# bcan_adapter.net
KiCad netlist of a schematic drawn in Altium Designer
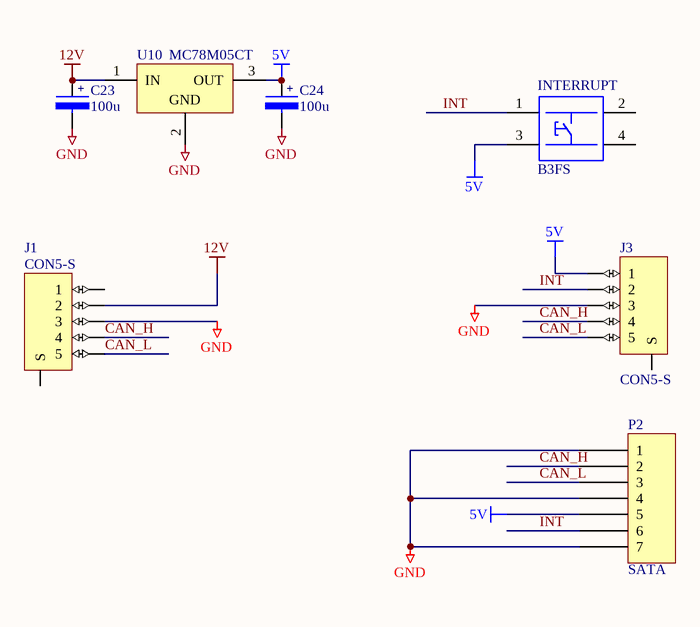
[diagram p0: bcan_adapter.SchDoc]

(export (version "E")
  (design (tool "Eeschema 10.0.6"))
  (components
    (comp (ref "C23")
      (value "100u")
      (footprint "HDR1X2C")
      (description "Capacitor")
      (libsource (lib "RCLDQ") (part "CAP-POL"))
    )
    (comp (ref "C24")
      (value "100u")
      (footprint "HDR1X2C")
      (description "Capacitor")
      (libsource (lib "RCLDQ") (part "CAP-POL"))
    )
    (comp (ref "INTERRUPT")
      (value "B3FS")
      (footprint "smd_switch")
      (description "SMD tactile switch")
      (libsource (lib "Miscellaneous") (part "B3FS"))
    )
    (comp (ref "J1")
      (value "CON5-S")
      (footprint "TRIAD5F")
      (description "Connector, 2 pin, with shield @ S")
      (libsource (lib "*") (part "CON5-S"))
    )
    (comp (ref "J3")
      (value "CON5-S")
      (footprint "TRIAD5F")
      (description "Connector, 2 pin, with shield @ S")
      (libsource (lib "") (part "CON5-S_1"))
    )
    (comp (ref "P2") (value "SATA") (footprint "47080-4005-SATA") (libsource (lib "BMS") (part "SATA")))
    (comp (ref "U10")
      (value "MC78M05CT")
      (footprint "TO-220-UP")
      (description "3-Terminal Medium-Current Positive Fixed Voltage Regulator")
      (fields (field (name "PUBLISHER") "Altium Limited"))
      (libsource (lib "Motorola Power Mgt Voltage Regulator") (part "MC78M05CT"))
    )
  )
  (nets
    (net (code "1") (name "/CAN_H") (class "Default")
      (node (ref "J1") (pin "4") (pinfunction "4_4") (pintype "bidirectional"))
      (node (ref "J3") (pin "4") (pinfunction "4_4") (pintype "bidirectional"))
      (node (ref "P2") (pin "2") (pinfunction "2_2") (pintype "passive"))
    )
    (net (code "2") (name "/CAN_L") (class "Default")
      (node (ref "J1") (pin "5") (pinfunction "5_5") (pintype "bidirectional"))
      (node (ref "J3") (pin "5") (pinfunction "5_5") (pintype "bidirectional"))
      (node (ref "P2") (pin "3") (pinfunction "3_3") (pintype "passive"))
    )
    (net (code "3") (name "/INT") (class "Default")
      (node (ref "INTERRUPT") (pin "1") (pinfunction "A1_1") (pintype "passive"))
      (node (ref "J3") (pin "2") (pinfunction "2_2") (pintype "bidirectional"))
      (node (ref "P2") (pin "6") (pinfunction "6_6") (pintype "passive"))
    )
    (net (code "4") (name "5V") (class "Default")
      (node (ref "C24") (pin "1") (pinfunction "1_1") (pintype "passive"))
      (node (ref "INTERRUPT") (pin "3") (pinfunction "B2_3") (pintype "passive"))
      (node (ref "J3") (pin "1") (pinfunction "1_1") (pintype "bidirectional"))
      (node (ref "P2") (pin "5") (pinfunction "5_5") (pintype "passive"))
      (node (ref "U10") (pin "3") (pinfunction "OUT_3") (pintype "power_in"))
    )
    (net (code "5") (name "12V") (class "Default")
      (node (ref "C23") (pin "1") (pinfunction "1_1") (pintype "passive"))
      (node (ref "J1") (pin "2") (pinfunction "2_2") (pintype "bidirectional"))
      (node (ref "U10") (pin "1") (pinfunction "IN_1") (pintype "power_in"))
    )
    (net (code "6") (name "GND") (class "Default")
      (node (ref "C23") (pin "2") (pinfunction "2_2") (pintype "passive"))
      (node (ref "C24") (pin "2") (pinfunction "2_2") (pintype "passive"))
      (node (ref "J1") (pin "3") (pinfunction "3_3") (pintype "bidirectional"))
      (node (ref "J3") (pin "3") (pinfunction "3_3") (pintype "bidirectional"))
      (node (ref "P2") (pin "1") (pinfunction "1_1") (pintype "passive"))
      (node (ref "P2") (pin "4") (pinfunction "4_4") (pintype "passive"))
      (node (ref "P2") (pin "7") (pinfunction "7_7") (pintype "passive"))
      (node (ref "U10") (pin "2") (pinfunction "GND_2") (pintype "power_in"))
    )
    (net (code "7") (name "unconnected-(INTERRUPT-A2-Pad2)") (class "Default")
      (node (ref "INTERRUPT") (pin "2") (pinfunction "A2_2") (pintype "passive"))
    )
    (net (code "8") (name "unconnected-(INTERRUPT-B1-Pad4)") (class "Default")
      (node (ref "INTERRUPT") (pin "4") (pinfunction "B1_4") (pintype "passive"))
    )
    (net (code "9") (name "unconnected-(J1-Pad1)") (class "Default")
      (node (ref "J1") (pin "1") (pinfunction "1_1") (pintype "bidirectional"))
    )
    (net (code "10") (name "unconnected-(J1-S-Pad0)") (class "Default")
      (node (ref "J1") (pin "0") (pinfunction "S_0") (pintype "bidirectional"))
    )
    (net (code "11") (name "unconnected-(J3-S-Pad0)") (class "Default")
      (node (ref "J3") (pin "0") (pinfunction "S_0") (pintype "bidirectional"))
    )
  )
)
